# hp6060bv1_5.net
KiCad netlist of a schematic drawn in EAGLE
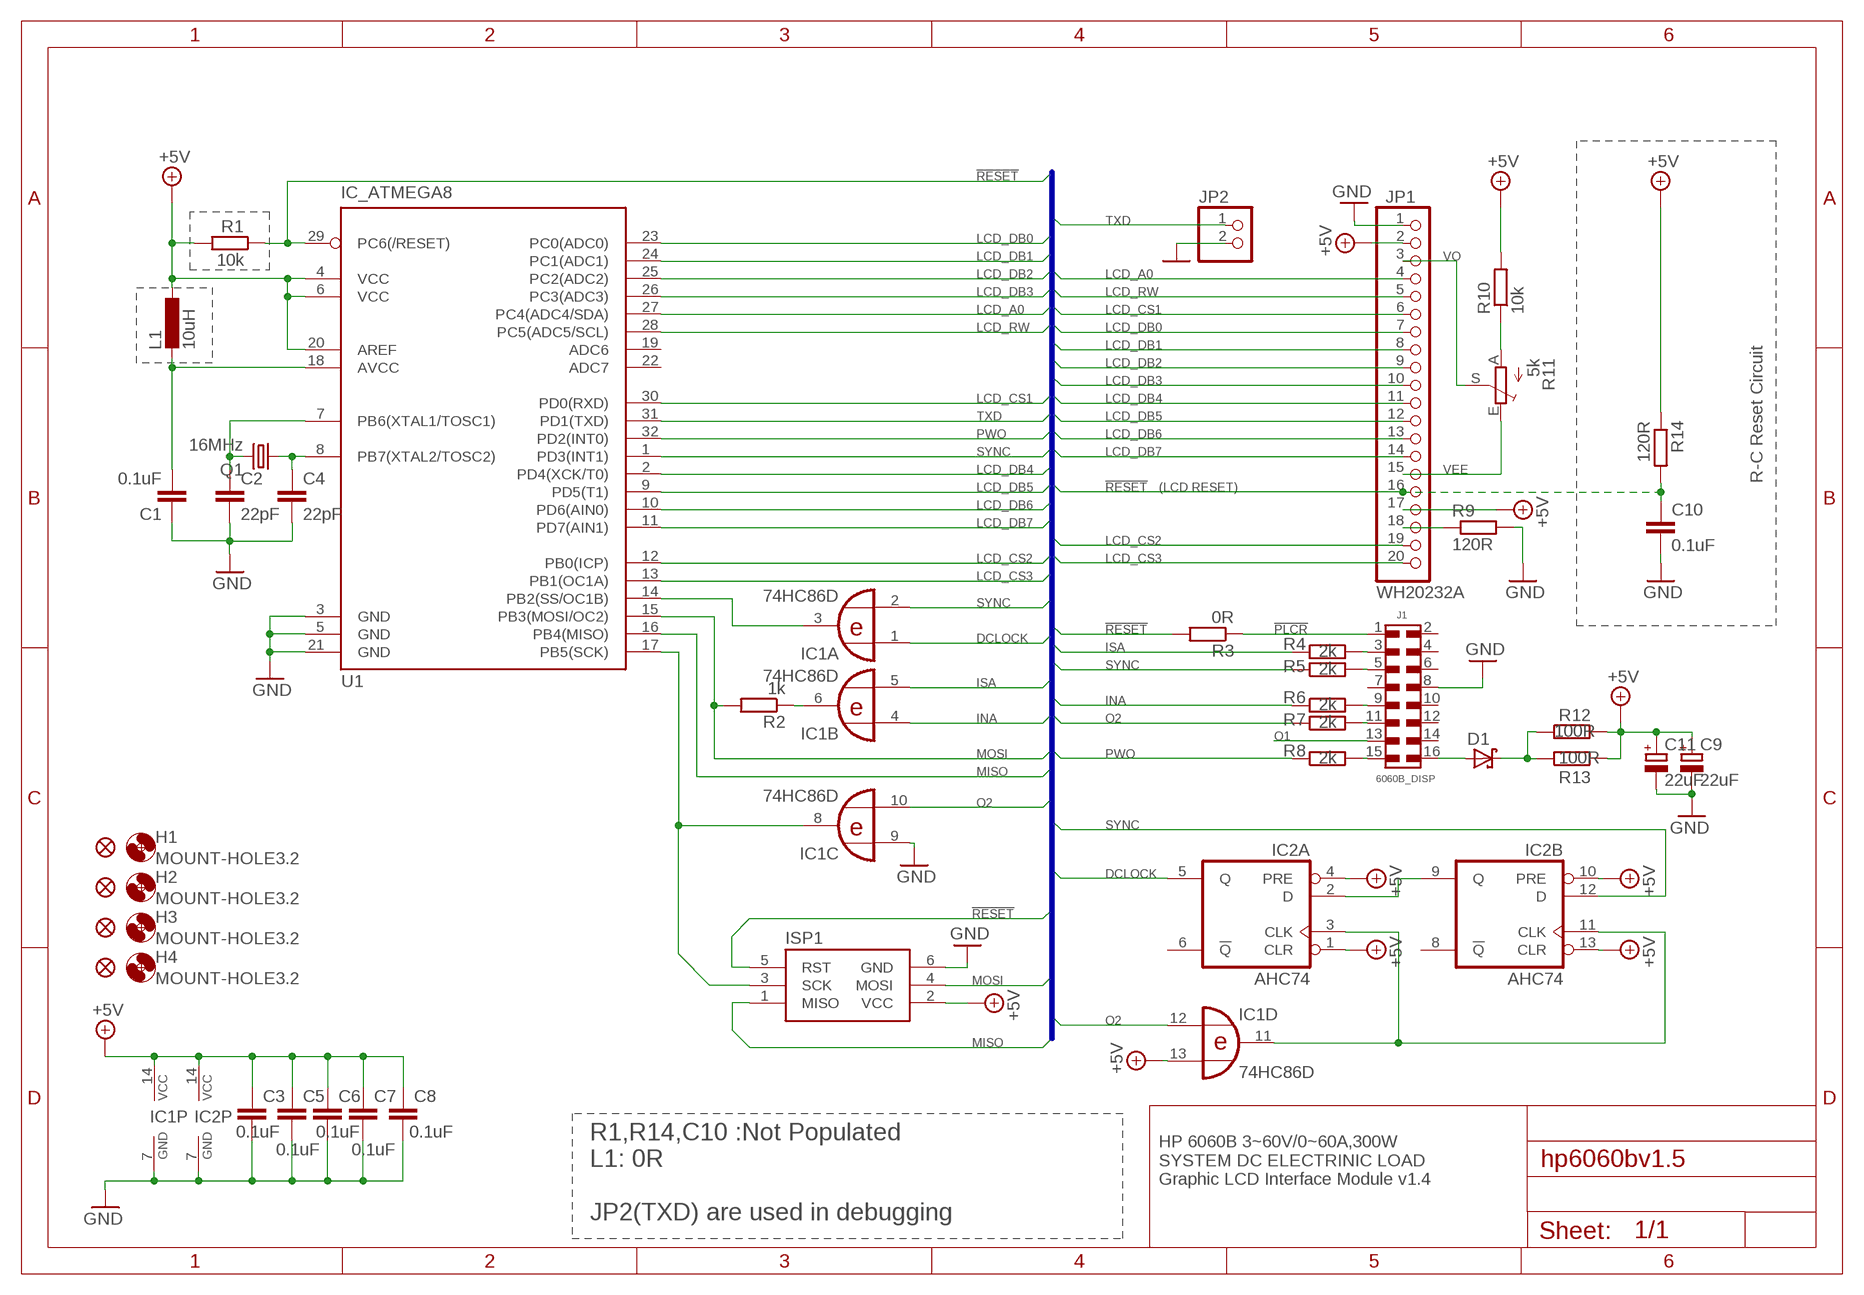
[diagram p0: schematic, sheet 1]

(export (version "E")
  (design (tool "Eeschema 10.0.6"))
  (components
    (comp (ref "C1")
      (value "0.1uF")
      (footprint "eagle-import:C1206")
      (libsource (lib "eagle-import") (part "C-EUC1206"))
    )
    (comp (ref "C2")
      (value "22pF")
      (footprint "eagle-import:C0603")
      (libsource (lib "eagle-import") (part "rcl_334_C-EUC0603"))
    )
    (comp (ref "C3")
      (value "0.1uF")
      (footprint "eagle-import:C1206")
      (libsource (lib "eagle-import") (part "rcl_334_C-EUC1206"))
    )
    (comp (ref "C4")
      (value "22pF")
      (footprint "eagle-import:C0603")
      (libsource (lib "eagle-import") (part "rcl_334_C-EUC0603"))
    )
    (comp (ref "C5")
      (value "0.1uF")
      (footprint "eagle-import:C1206")
      (libsource (lib "eagle-import") (part "rcl_334_C-EUC1206"))
    )
    (comp (ref "C6")
      (value "0.1uF")
      (footprint "eagle-import:C0805")
      (libsource (lib "eagle-import") (part "rcl_334_C-EUC0805"))
    )
    (comp (ref "C7")
      (value "0.1uF")
      (footprint "eagle-import:C0805")
      (libsource (lib "eagle-import") (part "rcl_334_C-EUC0805"))
    )
    (comp (ref "C8")
      (value "0.1uF")
      (footprint "eagle-import:C1206")
      (libsource (lib "eagle-import") (part "rcl_334_C-EUC1206"))
    )
    (comp (ref "C9")
      (value "22uF")
      (footprint "eagle-import:CT7343")
      (libsource (lib "eagle-import") (part "CPOL-EUCT7343"))
    )
    (comp (ref "C10")
      (value "0.1uF")
      (footprint "eagle-import:C0805")
      (libsource (lib "eagle-import") (part "rcl_334_C-EUC0805"))
    )
    (comp (ref "C11")
      (value "22uF")
      (footprint "eagle-import:CT7343")
      (libsource (lib "eagle-import") (part "CPOL-EUCT7343"))
    )
    (comp (ref "D1")
      (value "SCHOTTKY-DIODE")
      (footprint "eagle-import:DIODE_SMB")
      (libsource (lib "eagle-import") (part "SCHOTTKY-DIODE"))
    )
    (comp (ref "FID1")
      (value "PCB_FIDUCIALROUND")
      (footprint "eagle-import:PASS-ROUND")
      (libsource (lib "eagle-import") (part "PCB_FIDUCIALROUND"))
    )
    (comp (ref "FID2")
      (value "PCB_FIDUCIALROUND")
      (footprint "eagle-import:PASS-ROUND")
      (libsource (lib "eagle-import") (part "PCB_FIDUCIALROUND"))
    )
    (comp (ref "FID3")
      (value "PCB_FIDUCIALROUND")
      (footprint "eagle-import:PASS-ROUND")
      (libsource (lib "eagle-import") (part "PCB_FIDUCIALROUND"))
    )
    (comp (ref "FID4")
      (value "PCB_FIDUCIALROUND")
      (footprint "eagle-import:PASS-ROUND")
      (libsource (lib "eagle-import") (part "PCB_FIDUCIALROUND"))
    )
    (comp (ref "H1")
      (value "MOUNT-HOLE3.2")
      (footprint "eagle-import:3,2")
      (libsource (lib "eagle-import") (part "MOUNT-HOLE3.2"))
    )
    (comp (ref "H2")
      (value "MOUNT-HOLE3.2")
      (footprint "eagle-import:3,2")
      (libsource (lib "eagle-import") (part "MOUNT-HOLE3.2"))
    )
    (comp (ref "H3")
      (value "MOUNT-HOLE3.2")
      (footprint "eagle-import:3,2")
      (libsource (lib "eagle-import") (part "MOUNT-HOLE3.2"))
    )
    (comp (ref "H4")
      (value "MOUNT-HOLE3.2")
      (footprint "eagle-import:3,2")
      (libsource (lib "eagle-import") (part "MOUNT-HOLE3.2"))
    )
    (comp (ref "IC1")
      (value "74HC86D")
      (footprint "eagle-import:SO14")
      (libsource (lib "eagle-import") (part "7486DHC"))
    )
    (comp (ref "IC2")
      (value "AHC74")
      (footprint "eagle-import:TSSOP-14")
      (libsource (lib "eagle-import") (part "IC_HC74"))
    )
    (comp (ref "ISP1")
      (value "AVRISP-6")
      (footprint "eagle-import:AVRISP")
      (libsource (lib "eagle-import") (part "AVRISP-6"))
    )
    (comp (ref "J1")
      (value "6060B_DISP")
      (footprint "eagle-import:61001621121")
      (libsource (lib "eagle-import") (part "6100XX21121_61001621121"))
    )
    (comp (ref "JP1")
      (value "WH20232A")
      (footprint "eagle-import:1X20_ROUND")
      (libsource (lib "eagle-import") (part "HEADER-1X20ROUND"))
    )
    (comp (ref "JP2")
      (value "HEADER-1X2ROUND")
      (footprint "eagle-import:1X02_ROUND")
      (libsource (lib "eagle-import") (part "HEADER-1X2ROUND"))
    )
    (comp (ref "L1")
      (value "10uH")
      (footprint "eagle-import:L3225M")
      (libsource (lib "eagle-import") (part "L-EUL3225M"))
    )
    (comp (ref "Q1")
      (value "16MHz")
      (footprint "eagle-import:CSM-7X-DU")
      (libsource (lib "eagle-import") (part "CSM-7X-DU"))
    )
    (comp (ref "R1")
      (value "10k")
      (footprint "eagle-import:R1206")
      (libsource (lib "eagle-import") (part "R-EU_R1206"))
    )
    (comp (ref "R2")
      (value "1k")
      (footprint "eagle-import:R1206")
      (libsource (lib "eagle-import") (part "R-EU_R1206"))
    )
    (comp (ref "R3")
      (value "0R")
      (footprint "eagle-import:R1206")
      (libsource (lib "eagle-import") (part "R-EU_R1206"))
    )
    (comp (ref "R4")
      (value "2k")
      (footprint "eagle-import:R1206")
      (libsource (lib "eagle-import") (part "R-EU_R1206"))
    )
    (comp (ref "R5")
      (value "2k")
      (footprint "eagle-import:R1206")
      (libsource (lib "eagle-import") (part "R-EU_R1206"))
    )
    (comp (ref "R6")
      (value "2k")
      (footprint "eagle-import:R1206")
      (libsource (lib "eagle-import") (part "R-EU_R1206"))
    )
    (comp (ref "R7")
      (value "2k")
      (footprint "eagle-import:R1206")
      (libsource (lib "eagle-import") (part "R-EU_R1206"))
    )
    (comp (ref "R8")
      (value "2k")
      (footprint "eagle-import:R1206")
      (libsource (lib "eagle-import") (part "R-EU_R1206"))
    )
    (comp (ref "R9")
      (value "120R")
      (footprint "eagle-import:R1206")
      (libsource (lib "eagle-import") (part "R-EU_R1206"))
    )
    (comp (ref "R10")
      (value "10k")
      (footprint "eagle-import:R1206")
      (libsource (lib "eagle-import") (part "R-EU_R1206"))
    )
    (comp (ref "R11")
      (value "5k")
      (footprint "eagle-import:B25P")
      (libsource (lib "eagle-import") (part "TRIM_EU-B25P"))
    )
    (comp (ref "R12")
      (value "100R")
      (footprint "eagle-import:R1206")
      (libsource (lib "eagle-import") (part "R-EU_R1206"))
    )
    (comp (ref "R13")
      (value "100R")
      (footprint "eagle-import:R1206")
      (libsource (lib "eagle-import") (part "R-EU_R1206"))
    )
    (comp (ref "R14")
      (value "120R")
      (footprint "eagle-import:R0805")
      (libsource (lib "eagle-import") (part "R-EU_R0805"))
    )
    (comp (ref "U1")
      (value "IC_ATMEGA8")
      (footprint "eagle-import:LQFP32")
      (libsource (lib "eagle-import") (part "IC_ATMEGA8"))
    )
  )
  (nets
    (net (code "1") (name "+5V") (class "Default")
      (node (ref "C11") (pin "+") (pinfunction "+_+") (pintype "passive"))
      (node (ref "C3") (pin "1") (pinfunction "1_1") (pintype "passive"))
      (node (ref "C5") (pin "1") (pinfunction "1_1") (pintype "passive"))
      (node (ref "C6") (pin "1") (pinfunction "1_1") (pintype "passive"))
      (node (ref "C7") (pin "1") (pinfunction "1_1") (pintype "passive"))
      (node (ref "C8") (pin "1") (pinfunction "1_1") (pintype "passive"))
      (node (ref "C9") (pin "+") (pinfunction "+_+") (pintype "passive"))
      (node (ref "IC1") (pin "13") (pinfunction "I1_13") (pintype "input"))
      (node (ref "IC1") (pin "14") (pinfunction "VCC_14") (pintype "power_in"))
      (node (ref "IC2") (pin "1") (pinfunction "CLR_1") (pintype "input"))
      (node (ref "IC2") (pin "10") (pinfunction "PRE_10") (pintype "input"))
      (node (ref "IC2") (pin "13") (pinfunction "CLR_13") (pintype "input"))
      (node (ref "IC2") (pin "14") (pinfunction "VCC_14") (pintype "power_in"))
      (node (ref "IC2") (pin "4") (pinfunction "PRE_4") (pintype "input"))
      (node (ref "ISP1") (pin "2") (pinfunction "VCC_2") (pintype "power_in"))
      (node (ref "JP1") (pin "17") (pinfunction "17_17") (pintype "passive"))
      (node (ref "JP1") (pin "2") (pinfunction "2_2") (pintype "passive"))
      (node (ref "L1") (pin "1") (pinfunction "1_1") (pintype "passive"))
      (node (ref "R1") (pin "2") (pinfunction "2_2") (pintype "passive"))
      (node (ref "R10") (pin "2") (pinfunction "2_2") (pintype "passive"))
      (node (ref "R12") (pin "2") (pinfunction "2_2") (pintype "passive"))
      (node (ref "R13") (pin "2") (pinfunction "2_2") (pintype "passive"))
      (node (ref "R14") (pin "1") (pinfunction "1_1") (pintype "passive"))
      (node (ref "U1") (pin "20") (pinfunction "AREF_20") (pintype "passive"))
      (node (ref "U1") (pin "4") (pinfunction "VCC_4") (pintype "power_in"))
      (node (ref "U1") (pin "6") (pinfunction "VCC_6") (pintype "power_in"))
    )
    (net (code "2") (name "/DCLOCK") (class "Default")
      (node (ref "IC1") (pin "1") (pinfunction "I0_1") (pintype "input"))
      (node (ref "IC2") (pin "5") (pinfunction "Q_5") (pintype "output"))
    )
    (net (code "3") (name "/INA") (class "Default")
      (node (ref "IC1") (pin "4") (pinfunction "I0_4") (pintype "input"))
      (node (ref "R6") (pin "1") (pinfunction "1_1") (pintype "passive"))
    )
    (net (code "4") (name "/ISA") (class "Default")
      (node (ref "IC1") (pin "5") (pinfunction "I1_5") (pintype "input"))
      (node (ref "R4") (pin "1") (pinfunction "1_1") (pintype "passive"))
    )
    (net (code "5") (name "/LCD_A0") (class "Default")
      (node (ref "JP1") (pin "4") (pinfunction "4_4") (pintype "passive"))
      (node (ref "U1") (pin "27") (pinfunction "PC4(ADC4/SDA)_27") (pintype "bidirectional"))
    )
    (net (code "6") (name "/LCD_CS1") (class "Default")
      (node (ref "JP1") (pin "6") (pinfunction "6_6") (pintype "passive"))
      (node (ref "U1") (pin "30") (pinfunction "PD0(RXD)_30") (pintype "bidirectional"))
    )
    (net (code "7") (name "/LCD_CS2") (class "Default")
      (node (ref "JP1") (pin "19") (pinfunction "19_19") (pintype "passive"))
      (node (ref "U1") (pin "12") (pinfunction "PB0(ICP)_12") (pintype "bidirectional"))
    )
    (net (code "8") (name "/LCD_CS3") (class "Default")
      (node (ref "JP1") (pin "20") (pinfunction "20_20") (pintype "passive"))
      (node (ref "U1") (pin "13") (pinfunction "PB1(OC1A)_13") (pintype "bidirectional"))
    )
    (net (code "9") (name "/LCD_DB0") (class "Default")
      (node (ref "JP1") (pin "7") (pinfunction "7_7") (pintype "passive"))
      (node (ref "U1") (pin "23") (pinfunction "PC0(ADC0)_23") (pintype "bidirectional"))
    )
    (net (code "10") (name "/LCD_DB1") (class "Default")
      (node (ref "JP1") (pin "8") (pinfunction "8_8") (pintype "passive"))
      (node (ref "U1") (pin "24") (pinfunction "PC1(ADC1)_24") (pintype "bidirectional"))
    )
    (net (code "11") (name "/LCD_DB2") (class "Default")
      (node (ref "JP1") (pin "9") (pinfunction "9_9") (pintype "passive"))
      (node (ref "U1") (pin "25") (pinfunction "PC2(ADC2)_25") (pintype "bidirectional"))
    )
    (net (code "12") (name "/LCD_DB3") (class "Default")
      (node (ref "JP1") (pin "10") (pinfunction "10_10") (pintype "passive"))
      (node (ref "U1") (pin "26") (pinfunction "PC3(ADC3)_26") (pintype "bidirectional"))
    )
    (net (code "13") (name "/LCD_DB4") (class "Default")
      (node (ref "JP1") (pin "11") (pinfunction "11_11") (pintype "passive"))
      (node (ref "U1") (pin "2") (pinfunction "PD4(XCK/T0)_2") (pintype "bidirectional"))
    )
    (net (code "14") (name "/LCD_DB5") (class "Default")
      (node (ref "JP1") (pin "12") (pinfunction "12_12") (pintype "passive"))
      (node (ref "U1") (pin "9") (pinfunction "PD5(T1)_9") (pintype "bidirectional"))
    )
    (net (code "15") (name "/LCD_DB6") (class "Default")
      (node (ref "JP1") (pin "13") (pinfunction "13_13") (pintype "passive"))
      (node (ref "U1") (pin "10") (pinfunction "PD6(AIN0)_10") (pintype "bidirectional"))
    )
    (net (code "16") (name "/LCD_DB7") (class "Default")
      (node (ref "JP1") (pin "14") (pinfunction "14_14") (pintype "passive"))
      (node (ref "U1") (pin "11") (pinfunction "PD7(AIN1)_11") (pintype "bidirectional"))
    )
    (net (code "17") (name "/LCD_RW") (class "Default")
      (node (ref "JP1") (pin "5") (pinfunction "5_5") (pintype "passive"))
      (node (ref "U1") (pin "28") (pinfunction "PC5(ADC5/SCL)_28") (pintype "bidirectional"))
    )
    (net (code "18") (name "/MISO") (class "Default")
      (node (ref "ISP1") (pin "1") (pinfunction "MISO_1") (pintype "input"))
      (node (ref "U1") (pin "16") (pinfunction "PB4(MISO)_16") (pintype "bidirectional"))
    )
    (net (code "19") (name "/MOSI") (class "Default")
      (node (ref "ISP1") (pin "4") (pinfunction "MOSI_4") (pintype "output"))
      (node (ref "R2") (pin "2") (pinfunction "2_2") (pintype "passive"))
      (node (ref "U1") (pin "15") (pinfunction "PB3(MOSI/OC2)_15") (pintype "bidirectional"))
    )
    (net (code "20") (name "/O1") (class "Default")
      (node (ref "J1") (pin "13") (pinfunction "13_13") (pintype "passive"))
    )
    (net (code "21") (name "/O2") (class "Default")
      (node (ref "IC1") (pin "10") (pinfunction "I1_10") (pintype "input"))
      (node (ref "IC1") (pin "12") (pinfunction "I0_12") (pintype "input"))
      (node (ref "R7") (pin "1") (pinfunction "1_1") (pintype "passive"))
    )
    (net (code "22") (name "/PWO") (class "Default")
      (node (ref "R8") (pin "1") (pinfunction "1_1") (pintype "passive"))
      (node (ref "U1") (pin "32") (pinfunction "PD2(INT0)_32") (pintype "bidirectional"))
    )
    (net (code "23") (name "/SYNC") (class "Default")
      (node (ref "IC1") (pin "2") (pinfunction "I1_2") (pintype "input"))
      (node (ref "IC2") (pin "12") (pinfunction "D_12") (pintype "input"))
      (node (ref "R5") (pin "1") (pinfunction "1_1") (pintype "passive"))
      (node (ref "U1") (pin "1") (pinfunction "PD3(INT1)_1") (pintype "bidirectional"))
    )
    (net (code "24") (name "/TXD") (class "Default")
      (node (ref "JP2") (pin "1") (pinfunction "1_1") (pintype "passive"))
      (node (ref "U1") (pin "31") (pinfunction "PD1(TXD)_31") (pintype "bidirectional"))
    )
    (net (code "25") (name "/VEE") (class "Default")
      (node (ref "JP1") (pin "15") (pinfunction "15_15") (pintype "passive"))
      (node (ref "R11") (pin "E") (pinfunction "E_E") (pintype "passive"))
    )
    (net (code "26") (name "/VO") (class "Default")
      (node (ref "JP1") (pin "3") (pinfunction "3_3") (pintype "passive"))
      (node (ref "R11") (pin "S") (pinfunction "S_S") (pintype "passive"))
    )
    (net (code "27") (name "/~{PLCR}") (class "Default")
      (node (ref "J1") (pin "1") (pinfunction "1_1") (pintype "passive"))
      (node (ref "R3") (pin "1") (pinfunction "1_1") (pintype "passive"))
    )
    (net (code "28") (name "/~{RESET}") (class "Default")
      (node (ref "C10") (pin "1") (pinfunction "1_1") (pintype "passive"))
      (node (ref "ISP1") (pin "5") (pinfunction "RST_5") (pintype "output"))
      (node (ref "JP1") (pin "16") (pinfunction "16_16") (pintype "passive"))
      (node (ref "R1") (pin "1") (pinfunction "1_1") (pintype "passive"))
      (node (ref "R14") (pin "2") (pinfunction "2_2") (pintype "passive"))
      (node (ref "R3") (pin "2") (pinfunction "2_2") (pintype "passive"))
      (node (ref "U1") (pin "29") (pinfunction "PC6(/RESET)_29") (pintype "bidirectional"))
    )
    (net (code "29") (name "GND") (class "Default")
      (node (ref "C1") (pin "1") (pinfunction "1_1") (pintype "passive"))
      (node (ref "C10") (pin "2") (pinfunction "2_2") (pintype "passive"))
      (node (ref "C11") (pin "-") (pinfunction "-_-") (pintype "passive"))
      (node (ref "C2") (pin "2") (pinfunction "2_2") (pintype "passive"))
      (node (ref "C3") (pin "2") (pinfunction "2_2") (pintype "passive"))
      (node (ref "C4") (pin "2") (pinfunction "2_2") (pintype "passive"))
      (node (ref "C5") (pin "2") (pinfunction "2_2") (pintype "passive"))
      (node (ref "C6") (pin "2") (pinfunction "2_2") (pintype "passive"))
      (node (ref "C7") (pin "2") (pinfunction "2_2") (pintype "passive"))
      (node (ref "C8") (pin "2") (pinfunction "2_2") (pintype "passive"))
      (node (ref "C9") (pin "-") (pinfunction "-_-") (pintype "passive"))
      (node (ref "IC1") (pin "7") (pinfunction "GND_7") (pintype "power_in"))
      (node (ref "IC1") (pin "9") (pinfunction "I0_9") (pintype "input"))
      (node (ref "IC2") (pin "7") (pinfunction "GND_7") (pintype "power_in"))
      (node (ref "ISP1") (pin "6") (pinfunction "GND_6") (pintype "power_in"))
      (node (ref "J1") (pin "8") (pinfunction "8_8") (pintype "passive"))
      (node (ref "JP1") (pin "1") (pinfunction "1_1") (pintype "passive"))
      (node (ref "JP2") (pin "2") (pinfunction "2_2") (pintype "passive"))
      (node (ref "R9") (pin "2") (pinfunction "2_2") (pintype "passive"))
      (node (ref "U1") (pin "21") (pinfunction "GND_21") (pintype "power_in"))
      (node (ref "U1") (pin "3") (pinfunction "GND_3") (pintype "power_in"))
      (node (ref "U1") (pin "5") (pinfunction "GND_5") (pintype "power_in"))
    )
    (net (code "30") (name "Net-(D1-A)") (class "Default")
      (node (ref "D1") (pin "C") (pinfunction "A_C") (pintype "passive"))
      (node (ref "R12") (pin "1") (pinfunction "1_1") (pintype "passive"))
      (node (ref "R13") (pin "1") (pinfunction "1_1") (pintype "passive"))
    )
    (net (code "31") (name "Net-(D1-C)") (class "Default")
      (node (ref "D1") (pin "A") (pinfunction "C_A") (pintype "passive"))
      (node (ref "J1") (pin "16") (pinfunction "16_16") (pintype "passive"))
    )
    (net (code "32") (name "Net-(IC1A-O)") (class "Default")
      (node (ref "IC1") (pin "3") (pinfunction "O_3") (pintype "output"))
      (node (ref "U1") (pin "14") (pinfunction "PB2(SS/OC1B)_14") (pintype "bidirectional"))
    )
    (net (code "33") (name "Net-(IC1B-O)") (class "Default")
      (node (ref "IC1") (pin "6") (pinfunction "O_6") (pintype "output"))
      (node (ref "R2") (pin "1") (pinfunction "1_1") (pintype "passive"))
    )
    (net (code "34") (name "Net-(IC1C-O)") (class "Default")
      (node (ref "IC1") (pin "8") (pinfunction "O_8") (pintype "output"))
      (node (ref "ISP1") (pin "3") (pinfunction "SCK_3") (pintype "output"))
      (node (ref "U1") (pin "17") (pinfunction "PB5(SCK)_17") (pintype "bidirectional"))
    )
    (net (code "35") (name "Net-(IC1D-O)") (class "Default")
      (node (ref "IC1") (pin "11") (pinfunction "O_11") (pintype "output"))
      (node (ref "IC2") (pin "11") (pinfunction "CLK_11") (pintype "input"))
      (node (ref "IC2") (pin "3") (pinfunction "CLK_3") (pintype "input"))
    )
    (net (code "36") (name "Net-(IC2A-D)") (class "Default")
      (node (ref "IC2") (pin "2") (pinfunction "D_2") (pintype "input"))
      (node (ref "IC2") (pin "9") (pinfunction "Q_9") (pintype "output"))
    )
    (net (code "37") (name "Net-(J1-Pad3)") (class "Default")
      (node (ref "J1") (pin "3") (pinfunction "3_3") (pintype "passive"))
      (node (ref "R4") (pin "2") (pinfunction "2_2") (pintype "passive"))
    )
    (net (code "38") (name "Net-(J1-Pad5)") (class "Default")
      (node (ref "J1") (pin "5") (pinfunction "5_5") (pintype "passive"))
      (node (ref "R5") (pin "2") (pinfunction "2_2") (pintype "passive"))
    )
    (net (code "39") (name "Net-(J1-Pad9)") (class "Default")
      (node (ref "J1") (pin "9") (pinfunction "9_9") (pintype "passive"))
      (node (ref "R6") (pin "2") (pinfunction "2_2") (pintype "passive"))
    )
    (net (code "40") (name "Net-(J1-Pad11)") (class "Default")
      (node (ref "J1") (pin "11") (pinfunction "11_11") (pintype "passive"))
      (node (ref "R7") (pin "2") (pinfunction "2_2") (pintype "passive"))
    )
    (net (code "41") (name "Net-(J1-Pad15)") (class "Default")
      (node (ref "J1") (pin "15") (pinfunction "15_15") (pintype "passive"))
      (node (ref "R8") (pin "2") (pinfunction "2_2") (pintype "passive"))
    )
    (net (code "42") (name "Net-(JP1-Pad18)") (class "Default")
      (node (ref "JP1") (pin "18") (pinfunction "18_18") (pintype "passive"))
      (node (ref "R9") (pin "1") (pinfunction "1_1") (pintype "passive"))
    )
    (net (code "43") (name "Net-(R10-Pad1)") (class "Default")
      (node (ref "R10") (pin "1") (pinfunction "1_1") (pintype "passive"))
      (node (ref "R11") (pin "A") (pinfunction "A_A") (pintype "passive"))
    )
    (net (code "44") (name "Net-(U1-AVCC)") (class "Default")
      (node (ref "C1") (pin "2") (pinfunction "2_2") (pintype "passive"))
      (node (ref "L1") (pin "2") (pinfunction "2_2") (pintype "passive"))
      (node (ref "U1") (pin "18") (pinfunction "AVCC_18") (pintype "power_in"))
    )
    (net (code "45") (name "Net-(U1-PB6(XTAL1{slash}TOSC1))") (class "Default")
      (node (ref "C2") (pin "1") (pinfunction "1_1") (pintype "passive"))
      (node (ref "Q1") (pin "2") (pinfunction "2_2") (pintype "passive"))
      (node (ref "U1") (pin "7") (pinfunction "PB6(XTAL1/TOSC1)_7") (pintype "bidirectional"))
    )
    (net (code "46") (name "Net-(U1-PB7(XTAL2{slash}TOSC2))") (class "Default")
      (node (ref "C4") (pin "1") (pinfunction "1_1") (pintype "passive"))
      (node (ref "Q1") (pin "1") (pinfunction "1_1") (pintype "passive"))
      (node (ref "U1") (pin "8") (pinfunction "PB7(XTAL2/TOSC2)_8") (pintype "bidirectional"))
    )
    (net (code "47") (name "unconnected-(IC2A-~{Q}-Pad6)") (class "Default")
      (node (ref "IC2") (pin "6") (pinfunction "~{Q}_6") (pintype "output"))
    )
    (net (code "48") (name "unconnected-(IC2B-~{Q}-Pad8)") (class "Default")
      (node (ref "IC2") (pin "8") (pinfunction "~{Q}_8") (pintype "output"))
    )
    (net (code "49") (name "unconnected-(J1-Pad2)") (class "Default")
      (node (ref "J1") (pin "2") (pinfunction "2_2") (pintype "passive"))
    )
    (net (code "50") (name "unconnected-(J1-Pad4)") (class "Default")
      (node (ref "J1") (pin "4") (pinfunction "4_4") (pintype "passive"))
    )
    (net (code "51") (name "unconnected-(J1-Pad6)") (class "Default")
      (node (ref "J1") (pin "6") (pinfunction "6_6") (pintype "passive"))
    )
    (net (code "52") (name "unconnected-(J1-Pad7)") (class "Default")
      (node (ref "J1") (pin "7") (pinfunction "7_7") (pintype "passive"))
    )
    (net (code "53") (name "unconnected-(J1-Pad10)") (class "Default")
      (node (ref "J1") (pin "10") (pinfunction "10_10") (pintype "passive"))
    )
    (net (code "54") (name "unconnected-(J1-Pad12)") (class "Default")
      (node (ref "J1") (pin "12") (pinfunction "12_12") (pintype "passive"))
    )
    (net (code "55") (name "unconnected-(J1-Pad14)") (class "Default")
      (node (ref "J1") (pin "14") (pinfunction "14_14") (pintype "passive"))
    )
    (net (code "56") (name "unconnected-(U1-ADC6-Pad19)") (class "Default")
      (node (ref "U1") (pin "19") (pinfunction "ADC6_19") (pintype "bidirectional"))
    )
    (net (code "57") (name "unconnected-(U1-ADC7-Pad22)") (class "Default")
      (node (ref "U1") (pin "22") (pinfunction "ADC7_22") (pintype "bidirectional"))
    )
  )
)
